# SCH_SmartElectricFreqMonitor_2022-03-12.net
KiCad netlist of a schematic drawn in EasyEDA
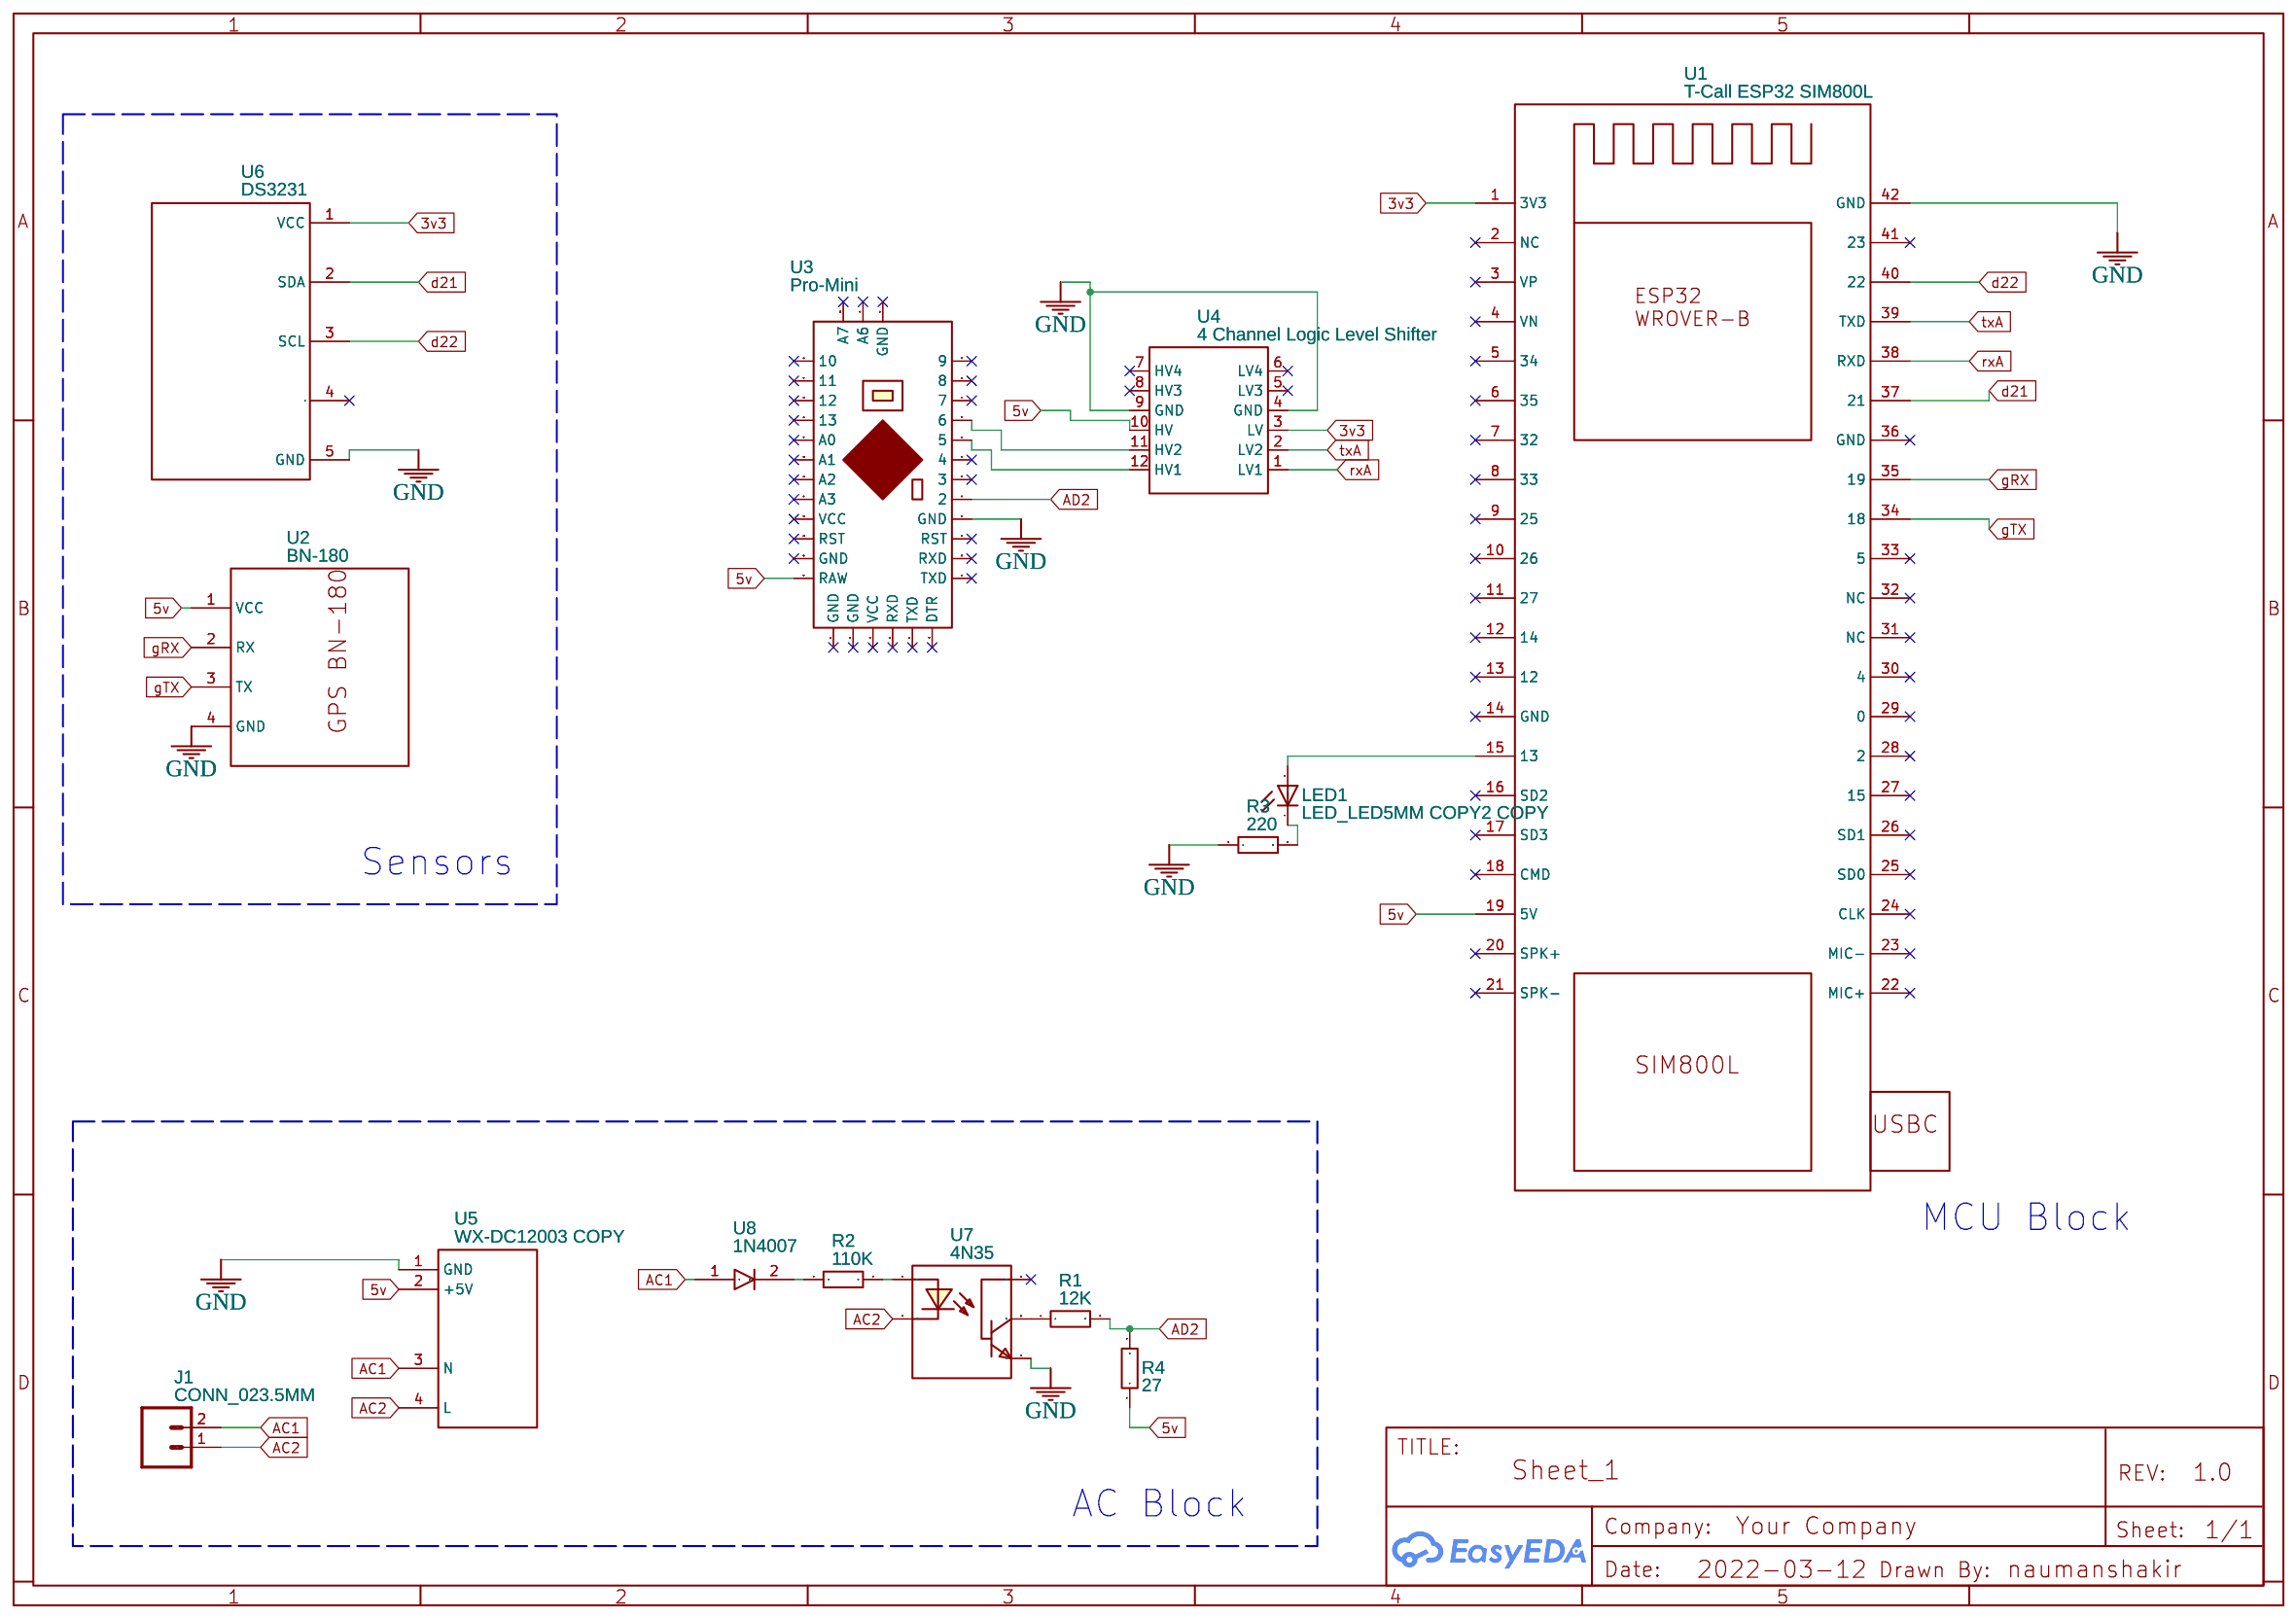
[diagram p0: schematic sheet]

(export (version "E")
  (design (tool "Eeschema 10.0.6"))
  (components
    (comp (ref "J1") (value "CONN_023.5MM") (libsource (lib "") (part "CONN_023.5MM")))
    (comp (ref "LED1") (value "LED_LED5MM COPY2 COPY") (libsource (lib "") (part "LED_LED5MM COPY2 COPY")))
    (comp (ref "R1")
      (value "12K")
      (fields
        (field (name "BOM_Manufacturer Part") "RD50T5123J")
        (field (name "BOM_Supplier Part") "C167534")
      )
      (libsource (lib "") (part "RD50T5123J"))
    )
    (comp (ref "R2")
      (value "110K")
      (fields (field (name "BOM_Supplier Part") "C120104"))
      (libsource (lib "") (part "CF1/4W-110KΩ±5% T52"))
    )
    (comp (ref "R3")
      (value "220")
      (fields
        (field (name "BOM_Manufacturer Part") "RD50T5221J")
        (field (name "BOM_Supplier Part") "C167559")
      )
      (libsource (lib "") (part "RD50T5221J"))
    )
    (comp (ref "R4")
      (value "27")
      (fields
        (field (name "BOM_Manufacturer Part") "RD50T5270J")
        (field (name "BOM_Supplier Part") "C167567")
      )
      (libsource (lib "") (part "RD50T5270J"))
    )
    (comp (ref "U1")
      (value "T-Call ESP32 SIM800L")
      (fields (field (name "BOM_Supplier Part") "ESP32 SIM800L"))
      (libsource (lib "") (part "T-Call ESP32 SIM800L"))
    )
    (comp (ref "U2") (value "BN-180") (libsource (lib "") (part "BN-180")))
    (comp (ref "U3") (value "Pro-Mini") (libsource (lib "") (part "Pro-Mini")))
    (comp (ref "U4")
      (value "4 Channel Logic Level Shifter")
      (libsource (lib "") (part "4 Channel Logic Level Shifter"))
    )
    (comp (ref "U5") (value "WX-DC12003 COPY") (libsource (lib "") (part "WX-DC12003 COPY")))
    (comp (ref "U6")
      (value "DS3231")
      (fields (field (name "BOM_Manufacturer Part") "New SchematicLib"))
      (libsource (lib "") (part "DS3231"))
    )
    (comp (ref "U7")
      (value "4N35")
      (fields (field (name "BOM_Supplier Part") "C57084"))
      (libsource (lib "") (part "4N35"))
    )
    (comp (ref "U8") (value "1N4007") (libsource (lib "") (part "1N4007")))
  )
  (nets
    (net (code "1") (name "3v3") (class "Default")
      (node (ref "U1") (pin "1") (pinfunction "3V3_1") (pintype "unspecified"))
      (node (ref "U4") (pin "3") (pinfunction "LV_3") (pintype "unspecified"))
      (node (ref "U6") (pin "1") (pinfunction "VCC_1") (pintype "unspecified"))
    )
    (net (code "2") (name "5v") (class "Default")
      (node (ref "R4") (pin "1") (pinfunction "1_1") (pintype "unspecified"))
      (node (ref "U1") (pin "19") (pinfunction "5V_19") (pintype "unspecified"))
      (node (ref "U2") (pin "1") (pinfunction "VCC_1") (pintype "unspecified"))
      (node (ref "U3") (pin "21") (pinfunction "RAW_21") (pintype "passive"))
      (node (ref "U4") (pin "10") (pinfunction "HV_10") (pintype "unspecified"))
      (node (ref "U5") (pin "2") (pinfunction "+5V_2") (pintype "unspecified"))
    )
    (net (code "3") (name "AC1") (class "Default")
      (node (ref "J1") (pin "2") (pinfunction "2_2") (pintype "bidirectional"))
      (node (ref "U5") (pin "3") (pinfunction "N_3") (pintype "unspecified"))
      (node (ref "U8") (pin "1") (pinfunction "1_1") (pintype "unspecified"))
    )
    (net (code "4") (name "AC2") (class "Default")
      (node (ref "J1") (pin "1") (pinfunction "1_1") (pintype "bidirectional"))
      (node (ref "U5") (pin "4") (pinfunction "L_4") (pintype "unspecified"))
      (node (ref "U7") (pin "2") (pinfunction "2_2") (pintype "unspecified"))
    )
    (net (code "5") (name "AD2") (class "Default")
      (node (ref "R1") (pin "2") (pinfunction "2_2") (pintype "unspecified"))
      (node (ref "R4") (pin "2") (pinfunction "2_2") (pintype "unspecified"))
      (node (ref "U3") (pin "2") (pinfunction "2_2") (pintype "bidirectional"))
    )
    (net (code "6") (name "GND") (class "Default")
      (node (ref "R3") (pin "1") (pinfunction "1_1") (pintype "unspecified"))
      (node (ref "U1") (pin "42") (pinfunction "GND_42") (pintype "unspecified"))
      (node (ref "U2") (pin "4") (pinfunction "GND_4") (pintype "unspecified"))
      (node (ref "U3") (pin "23") (pinfunction "GND_23") (pintype "passive"))
      (node (ref "U4") (pin "4") (pinfunction "GND_4") (pintype "unspecified"))
      (node (ref "U4") (pin "9") (pinfunction "GND_9") (pintype "unspecified"))
      (node (ref "U5") (pin "1") (pinfunction "GND_1") (pintype "unspecified"))
      (node (ref "U6") (pin "5") (pinfunction "GND_5") (pintype "unspecified"))
      (node (ref "U7") (pin "4") (pinfunction "4_4") (pintype "unspecified"))
    )
    (net (code "7") (name "Net-(LED1-C)") (class "Default")
      (node (ref "LED1") (pin "K") (pinfunction "C_K") (pintype "unspecified"))
      (node (ref "R3") (pin "2") (pinfunction "2_2") (pintype "unspecified"))
    )
    (net (code "8") (name "Net-(R1-Pad1)") (class "Default")
      (node (ref "R1") (pin "1") (pinfunction "1_1") (pintype "unspecified"))
      (node (ref "U7") (pin "5") (pinfunction "5_5") (pintype "unspecified"))
    )
    (net (code "9") (name "Net-(R2-Pad1)") (class "Default")
      (node (ref "R2") (pin "1") (pinfunction "1_1") (pintype "unspecified"))
      (node (ref "U8") (pin "2") (pinfunction "2_2") (pintype "unspecified"))
    )
    (net (code "10") (name "Net-(R2-Pad2)") (class "Default")
      (node (ref "R2") (pin "2") (pinfunction "2_2") (pintype "unspecified"))
      (node (ref "U7") (pin "1") (pinfunction "1_1") (pintype "unspecified"))
    )
    (net (code "11") (name "Net-(U1-13)") (class "Default")
      (node (ref "LED1") (pin "A") (pinfunction "A_A") (pintype "unspecified"))
      (node (ref "U1") (pin "15") (pinfunction "13_15") (pintype "unspecified"))
    )
    (net (code "12") (name "Net-(U4-HV1)") (class "Default")
      (node (ref "U3") (pin "5") (pinfunction "5_5") (pintype "bidirectional"))
      (node (ref "U4") (pin "12") (pinfunction "HV1_12") (pintype "unspecified"))
    )
    (net (code "13") (name "Net-(U4-HV2)") (class "Default")
      (node (ref "U3") (pin "6") (pinfunction "6_6") (pintype "bidirectional"))
      (node (ref "U4") (pin "11") (pinfunction "HV2_11") (pintype "unspecified"))
    )
    (net (code "14") (name "d21") (class "Default")
      (node (ref "U1") (pin "37") (pinfunction "21_37") (pintype "unspecified"))
      (node (ref "U6") (pin "2") (pinfunction "SDA_2") (pintype "unspecified"))
    )
    (net (code "15") (name "d22") (class "Default")
      (node (ref "U1") (pin "40") (pinfunction "22_40") (pintype "unspecified"))
      (node (ref "U6") (pin "3") (pinfunction "SCL_3") (pintype "unspecified"))
    )
    (net (code "16") (name "gRX") (class "Default")
      (node (ref "U1") (pin "35") (pinfunction "19_35") (pintype "unspecified"))
      (node (ref "U2") (pin "2") (pinfunction "RX_2") (pintype "unspecified"))
    )
    (net (code "17") (name "gTX") (class "Default")
      (node (ref "U1") (pin "34") (pinfunction "18_34") (pintype "unspecified"))
      (node (ref "U2") (pin "3") (pinfunction "TX_3") (pintype "unspecified"))
    )
    (net (code "18") (name "rxA") (class "Default")
      (node (ref "U1") (pin "38") (pinfunction "RXD_38") (pintype "unspecified"))
      (node (ref "U4") (pin "1") (pinfunction "LV1_1") (pintype "unspecified"))
    )
    (net (code "19") (name "txA") (class "Default")
      (node (ref "U1") (pin "39") (pinfunction "TXD_39") (pintype "unspecified"))
      (node (ref "U4") (pin "2") (pinfunction "LV2_2") (pintype "unspecified"))
    )
    (net (code "20") (name "unconnected-(U1-0-Pad29)") (class "Default")
      (node (ref "U1") (pin "29") (pinfunction "0_29") (pintype "unspecified+no_connect"))
    )
    (net (code "21") (name "unconnected-(U1-2-Pad28)") (class "Default")
      (node (ref "U1") (pin "28") (pinfunction "2_28") (pintype "unspecified+no_connect"))
    )
    (net (code "22") (name "unconnected-(U1-4-Pad30)") (class "Default")
      (node (ref "U1") (pin "30") (pinfunction "4_30") (pintype "unspecified+no_connect"))
    )
    (net (code "23") (name "unconnected-(U1-5-Pad33)") (class "Default")
      (node (ref "U1") (pin "33") (pinfunction "5_33") (pintype "unspecified+no_connect"))
    )
    (net (code "24") (name "unconnected-(U1-12-Pad13)") (class "Default")
      (node (ref "U1") (pin "13") (pinfunction "12_13") (pintype "unspecified+no_connect"))
    )
    (net (code "25") (name "unconnected-(U1-14-Pad12)") (class "Default")
      (node (ref "U1") (pin "12") (pinfunction "14_12") (pintype "unspecified+no_connect"))
    )
    (net (code "26") (name "unconnected-(U1-15-Pad27)") (class "Default")
      (node (ref "U1") (pin "27") (pinfunction "15_27") (pintype "unspecified+no_connect"))
    )
    (net (code "27") (name "unconnected-(U1-23-Pad41)") (class "Default")
      (node (ref "U1") (pin "41") (pinfunction "23_41") (pintype "unspecified+no_connect"))
    )
    (net (code "28") (name "unconnected-(U1-25-Pad9)") (class "Default")
      (node (ref "U1") (pin "9") (pinfunction "25_9") (pintype "unspecified+no_connect"))
    )
    (net (code "29") (name "unconnected-(U1-26-Pad10)") (class "Default")
      (node (ref "U1") (pin "10") (pinfunction "26_10") (pintype "unspecified+no_connect"))
    )
    (net (code "30") (name "unconnected-(U1-27-Pad11)") (class "Default")
      (node (ref "U1") (pin "11") (pinfunction "27_11") (pintype "unspecified+no_connect"))
    )
    (net (code "31") (name "unconnected-(U1-32-Pad7)") (class "Default")
      (node (ref "U1") (pin "7") (pinfunction "32_7") (pintype "unspecified+no_connect"))
    )
    (net (code "32") (name "unconnected-(U1-33-Pad8)") (class "Default")
      (node (ref "U1") (pin "8") (pinfunction "33_8") (pintype "unspecified+no_connect"))
    )
    (net (code "33") (name "unconnected-(U1-34-Pad5)") (class "Default")
      (node (ref "U1") (pin "5") (pinfunction "34_5") (pintype "unspecified+no_connect"))
    )
    (net (code "34") (name "unconnected-(U1-35-Pad6)") (class "Default")
      (node (ref "U1") (pin "6") (pinfunction "35_6") (pintype "unspecified+no_connect"))
    )
    (net (code "35") (name "unconnected-(U1-CLK-Pad24)") (class "Default")
      (node (ref "U1") (pin "24") (pinfunction "CLK_24") (pintype "unspecified+no_connect"))
    )
    (net (code "36") (name "unconnected-(U1-CMD-Pad18)") (class "Default")
      (node (ref "U1") (pin "18") (pinfunction "CMD_18") (pintype "unspecified+no_connect"))
    )
    (net (code "37") (name "unconnected-(U1-GND-Pad14)") (class "Default")
      (node (ref "U1") (pin "14") (pinfunction "GND_14") (pintype "unspecified+no_connect"))
    )
    (net (code "38") (name "unconnected-(U1-GND-Pad36)") (class "Default")
      (node (ref "U1") (pin "36") (pinfunction "GND_36") (pintype "unspecified+no_connect"))
    )
    (net (code "39") (name "unconnected-(U1-MIC+-Pad22)") (class "Default")
      (node (ref "U1") (pin "22") (pinfunction "MIC+_22") (pintype "unspecified+no_connect"))
    )
    (net (code "40") (name "unconnected-(U1-MIC--Pad23)") (class "Default")
      (node (ref "U1") (pin "23") (pinfunction "MIC-_23") (pintype "unspecified+no_connect"))
    )
    (net (code "41") (name "unconnected-(U1-NC-Pad2)") (class "Default")
      (node (ref "U1") (pin "2") (pinfunction "NC_2") (pintype "unspecified+no_connect"))
    )
    (net (code "42") (name "unconnected-(U1-NC-Pad31)") (class "Default")
      (node (ref "U1") (pin "31") (pinfunction "NC_31") (pintype "unspecified+no_connect"))
    )
    (net (code "43") (name "unconnected-(U1-NC-Pad32)") (class "Default")
      (node (ref "U1") (pin "32") (pinfunction "NC_32") (pintype "unspecified+no_connect"))
    )
    (net (code "44") (name "unconnected-(U1-SD0-Pad25)") (class "Default")
      (node (ref "U1") (pin "25") (pinfunction "SD0_25") (pintype "unspecified+no_connect"))
    )
    (net (code "45") (name "unconnected-(U1-SD1-Pad26)") (class "Default")
      (node (ref "U1") (pin "26") (pinfunction "SD1_26") (pintype "unspecified+no_connect"))
    )
    (net (code "46") (name "unconnected-(U1-SD2-Pad16)") (class "Default")
      (node (ref "U1") (pin "16") (pinfunction "SD2_16") (pintype "unspecified+no_connect"))
    )
    (net (code "47") (name "unconnected-(U1-SD3-Pad17)") (class "Default")
      (node (ref "U1") (pin "17") (pinfunction "SD3_17") (pintype "unspecified+no_connect"))
    )
    (net (code "48") (name "unconnected-(U1-SPK+-Pad20)") (class "Default")
      (node (ref "U1") (pin "20") (pinfunction "SPK+_20") (pintype "unspecified+no_connect"))
    )
    (net (code "49") (name "unconnected-(U1-SPK--Pad21)") (class "Default")
      (node (ref "U1") (pin "21") (pinfunction "SPK-_21") (pintype "unspecified+no_connect"))
    )
    (net (code "50") (name "unconnected-(U1-VN-Pad4)") (class "Default")
      (node (ref "U1") (pin "4") (pinfunction "VN_4") (pintype "unspecified+no_connect"))
    )
    (net (code "51") (name "unconnected-(U1-VP-Pad3)") (class "Default")
      (node (ref "U1") (pin "3") (pinfunction "VP_3") (pintype "unspecified+no_connect"))
    )
    (net (code "52") (name "unconnected-(U3-A0-Pad14)") (class "Default")
      (node (ref "U3") (pin "14") (pinfunction "A0_14") (pintype "bidirectional+no_connect"))
    )
    (net (code "53") (name "unconnected-(U3-A1-Pad15)") (class "Default")
      (node (ref "U3") (pin "15") (pinfunction "A1_15") (pintype "bidirectional+no_connect"))
    )
    (net (code "54") (name "unconnected-(U3-A2-Pad16)") (class "Default")
      (node (ref "U3") (pin "16") (pinfunction "A2_16") (pintype "bidirectional+no_connect"))
    )
    (net (code "55") (name "unconnected-(U3-A3-Pad17)") (class "Default")
      (node (ref "U3") (pin "17") (pinfunction "A3_17") (pintype "bidirectional+no_connect"))
    )
    (net (code "56") (name "unconnected-(U3-A6-Pad27)") (class "Default")
      (node (ref "U3") (pin "27") (pinfunction "A6_27") (pintype "bidirectional+no_connect"))
    )
    (net (code "57") (name "unconnected-(U3-A7-Pad28)") (class "Default")
      (node (ref "U3") (pin "28") (pinfunction "A7_28") (pintype "bidirectional+no_connect"))
    )
    (net (code "58") (name "unconnected-(U3-DTR-Pad30)") (class "Default")
      (node (ref "U3") (pin "30") (pinfunction "DTR_30") (pintype "unspecified+no_connect"))
    )
    (net (code "59") (name "unconnected-(U3-GND-Pad20)") (class "Default")
      (node (ref "U3") (pin "20") (pinfunction "GND_20") (pintype "passive+no_connect"))
    )
    (net (code "60") (name "unconnected-(U3-GND-Pad24)") (class "Default")
      (node (ref "U3") (pin "24") (pinfunction "GND_24") (pintype "passive+no_connect"))
    )
    (net (code "61") (name "unconnected-(U3-GND-Pad34)") (class "Default")
      (node (ref "U3") (pin "34") (pinfunction "GND_34") (pintype "unspecified+no_connect"))
    )
    (net (code "62") (name "unconnected-(U3-GND-Pad35)") (class "Default")
      (node (ref "U3") (pin "35") (pinfunction "GND_35") (pintype "unspecified+no_connect"))
    )
    (net (code "63") (name "unconnected-(U3-Pad3)") (class "Default")
      (node (ref "U3") (pin "3") (pinfunction "3_3") (pintype "bidirectional+no_connect"))
    )
    (net (code "64") (name "unconnected-(U3-Pad4)") (class "Default")
      (node (ref "U3") (pin "4") (pinfunction "4_4") (pintype "bidirectional+no_connect"))
    )
    (net (code "65") (name "unconnected-(U3-Pad7)") (class "Default")
      (node (ref "U3") (pin "7") (pinfunction "7_7") (pintype "bidirectional+no_connect"))
    )
    (net (code "66") (name "unconnected-(U3-Pad8)") (class "Default")
      (node (ref "U3") (pin "8") (pinfunction "8_8") (pintype "bidirectional+no_connect"))
    )
    (net (code "67") (name "unconnected-(U3-Pad9)") (class "Default")
      (node (ref "U3") (pin "9") (pinfunction "9_9") (pintype "bidirectional+no_connect"))
    )
    (net (code "68") (name "unconnected-(U3-Pad10)") (class "Default")
      (node (ref "U3") (pin "10") (pinfunction "10_10") (pintype "bidirectional+no_connect"))
    )
    (net (code "69") (name "unconnected-(U3-Pad11)") (class "Default")
      (node (ref "U3") (pin "11") (pinfunction "11_11") (pintype "bidirectional+no_connect"))
    )
    (net (code "70") (name "unconnected-(U3-Pad12)") (class "Default")
      (node (ref "U3") (pin "12") (pinfunction "12_12") (pintype "bidirectional+no_connect"))
    )
    (net (code "71") (name "unconnected-(U3-Pad13)") (class "Default")
      (node (ref "U3") (pin "13") (pinfunction "13_13") (pintype "bidirectional+no_connect"))
    )
    (net (code "72") (name "unconnected-(U3-RST-Pad19)") (class "Default")
      (node (ref "U3") (pin "19") (pinfunction "RST_19") (pintype "input+no_connect"))
    )
    (net (code "73") (name "unconnected-(U3-RST-Pad22)") (class "Default")
      (node (ref "U3") (pin "22") (pinfunction "RST_22") (pintype "input+no_connect"))
    )
    (net (code "74") (name "unconnected-(U3-RXD-Pad0)") (class "Default")
      (node (ref "U3") (pin "0") (pinfunction "RXD_0") (pintype "input+no_connect"))
    )
    (net (code "75") (name "unconnected-(U3-RXD-Pad32)") (class "Default")
      (node (ref "U3") (pin "32") (pinfunction "RXD_32") (pintype "unspecified+no_connect"))
    )
    (net (code "76") (name "unconnected-(U3-TXD-Pad1)") (class "Default")
      (node (ref "U3") (pin "1") (pinfunction "TXD_1") (pintype "output+no_connect"))
    )
    (net (code "77") (name "unconnected-(U3-TXD-Pad31)") (class "Default")
      (node (ref "U3") (pin "31") (pinfunction "TXD_31") (pintype "unspecified+no_connect"))
    )
    (net (code "78") (name "unconnected-(U3-VCC-Pad18)") (class "Default")
      (node (ref "U3") (pin "18") (pinfunction "VCC_18") (pintype "passive+no_connect"))
    )
    (net (code "79") (name "unconnected-(U3-VCC-Pad33)") (class "Default")
      (node (ref "U3") (pin "33") (pinfunction "VCC_33") (pintype "unspecified+no_connect"))
    )
    (net (code "80") (name "unconnected-(U4-HV3-Pad8)") (class "Default")
      (node (ref "U4") (pin "8") (pinfunction "HV3_8") (pintype "unspecified+no_connect"))
    )
    (net (code "81") (name "unconnected-(U4-HV4-Pad7)") (class "Default")
      (node (ref "U4") (pin "7") (pinfunction "HV4_7") (pintype "unspecified+no_connect"))
    )
    (net (code "82") (name "unconnected-(U4-LV3-Pad5)") (class "Default")
      (node (ref "U4") (pin "5") (pinfunction "LV3_5") (pintype "unspecified+no_connect"))
    )
    (net (code "83") (name "unconnected-(U4-LV4-Pad6)") (class "Default")
      (node (ref "U4") (pin "6") (pinfunction "LV4_6") (pintype "unspecified+no_connect"))
    )
    (net (code "84") (name "unconnected-(U6-Pad4)") (class "Default")
      (node (ref "U6") (pin "4") (pinfunction "4_4") (pintype "unspecified+no_connect"))
    )
    (net (code "85") (name "unconnected-(U7-Pad6)") (class "Default")
      (node (ref "U7") (pin "6") (pinfunction "6_6") (pintype "unspecified+no_connect"))
    )
  )
)
